# SH10_-_CAN.net
KiCad netlist of a schematic drawn in Altium Designer
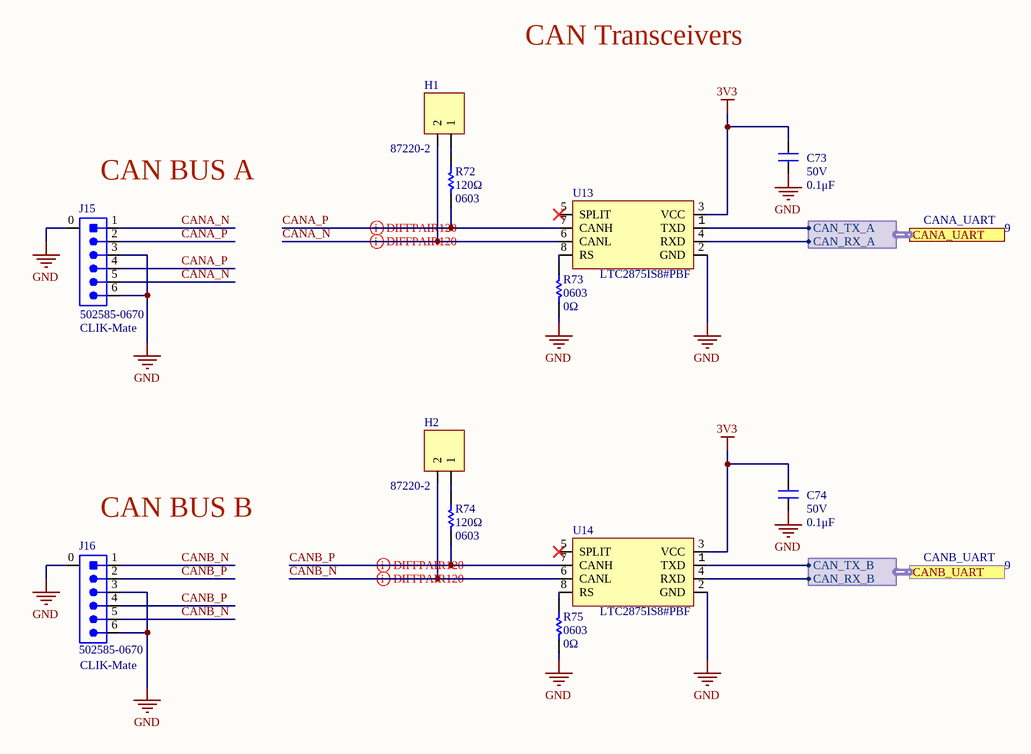
[diagram p0: SH10 - CAN.SchDoc]

(export (version "E")
  (design (tool "Eeschema 10.0.6"))
  (components
    (comp (ref "C73")
      (value "0.1μF")
      (footprint "CAP0603")
      (description "CAP CER 0.1UF 50V X7R 0603")
      (fields (field (name "VOLTAGE RATING") "50V") (field (name "Comment") "CAP_0.1uF_50V_0603"))
      (libsource (lib "UWRT_Schematic_Library_2020") (part "CAP_0.1uF_50V_0603"))
    )
    (comp (ref "C74")
      (value "0.1μF")
      (footprint "CAP0603")
      (description "CAP CER 0.1UF 50V X7R 0603")
      (fields (field (name "VOLTAGE RATING") "50V") (field (name "Comment") "CAP_0.1uF_50V_0603"))
      (libsource (lib "UWRT_Schematic_Library_2020") (part "CAP_0.1uF_50V_0603"))
    )
    (comp (ref "H1")
      (value "JUMPER_2")
      (footprint "HDR1X2")
      (description "HEADER 2X1")
      (fields (field (name "MANUFACTURER PART NUMBER 1") "87220-2"))
      (libsource (lib "UWRT_Schematic_Library_2020") (part "JUMPER_2"))
    )
    (comp (ref "H2")
      (value "JUMPER_2")
      (footprint "HDR1X2")
      (description "HEADER 2X1")
      (fields (field (name "MANUFACTURER PART NUMBER 1") "87220-2"))
      (libsource (lib "UWRT_Schematic_Library_2020") (part "JUMPER_2"))
    )
    (comp (ref "J15")
      (value "CON_6M_SM_RA_1.5mm")
      (footprint "MOLEX-5025850670")
      (description "CONN HEADER SMD RIGHT ANGLE 1.5 MM PITCH")
      (fields
        (field (name "MANUFACTOR NUMBER") "502585-0670")
        (field (name "MANUFACTURER") "Molex")
        (field (name "FAMILY") "CLIK-Mate")
      )
      (libsource (lib "UWRT_Schematic_Library_2020") (part "CON_6M_SM_RA_1.5mm"))
    )
    (comp (ref "J16")
      (value "CON_6M_SM_RA_1.5mm")
      (footprint "MOLEX-5025850670")
      (description "CONN HEADER SMD RIGHT ANGLE 1.5 MM PITCH")
      (fields
        (field (name "MANUFACTOR NUMBER") "502585-0670")
        (field (name "MANUFACTURER") "Molex")
        (field (name "FAMILY") "CLIK-Mate")
      )
      (libsource (lib "UWRT_Schematic_Library_2020") (part "CON_6M_SM_RA_1.5mm"))
    )
    (comp (ref "R72")
      (value "120Ω")
      (footprint "RESC0603(1608)_N")
      (description "RES 120 OHM 5% 1/10W 0603")
      (fields
        (field (name "TOLERANCE") "5%")
        (field (name "CASE CODE (IMPERIAL)") "0603")
        (field (name "Comment") "RES_120Ω_0603")
      )
      (libsource (lib "UWRT_Schematic_Library_2020") (part "RES_120Ω_0603_5%"))
    )
    (comp (ref "R73")
      (value "0Ω")
      (footprint "RESC0603(1608)_N")
      (description "RES 0 OHM JUMPER 1/10W 0603")
      (fields (field (name "CASE CODE (IMPERIAL)") "0603") (field (name "Comment") "RES_0Ω_0603"))
      (libsource (lib "UWRT_Schematic_Library_2020") (part "RES_0Ω_0603"))
    )
    (comp (ref "R74")
      (value "120Ω")
      (footprint "RESC0603(1608)_N")
      (description "RES 120 OHM 5% 1/10W 0603")
      (fields
        (field (name "TOLERANCE") "5%")
        (field (name "CASE CODE (IMPERIAL)") "0603")
        (field (name "Comment") "RES_120Ω_0603")
      )
      (libsource (lib "UWRT_Schematic_Library_2020") (part "RES_120Ω_0603_5%"))
    )
    (comp (ref "R75")
      (value "0Ω")
      (footprint "RESC0603(1608)_N")
      (description "RES 0 OHM JUMPER 1/10W 0603")
      (fields (field (name "CASE CODE (IMPERIAL)") "0603") (field (name "Comment") "RES_0Ω_0603"))
      (libsource (lib "UWRT_Schematic_Library_2020") (part "RES_0Ω_0603"))
    )
    (comp (ref "U13")
      (value "IC TXRX CAN")
      (footprint "LT-S8_N")
      (description "IC TXRX CAN 4MBPS 8SO")
      (fields (field (name "MANUFACTURER PART NUMBER 1") "LTC2875IS8#PBF"))
      (libsource (lib "UWRT_Schematic_Library_2020") (part "LTC2875"))
    )
    (comp (ref "U14")
      (value "IC TXRX CAN")
      (footprint "LT-S8_N")
      (description "IC TXRX CAN 4MBPS 8SO")
      (fields (field (name "MANUFACTURER PART NUMBER 1") "LTC2875IS8#PBF"))
      (libsource (lib "UWRT_Schematic_Library_2020") (part "LTC2875"))
    )
  )
  (nets
    (net (code "3") (name "/CANA_N") (class "Default")
      (node (ref "H1") (pin "2") (pinfunction "2_2") (pintype "passive"))
      (node (ref "J15") (pin "1") (pinfunction "1_1") (pintype "passive"))
      (node (ref "J15") (pin "5") (pinfunction "5_5") (pintype "passive"))
      (node (ref "U13") (pin "6") (pinfunction "CANL_6") (pintype "passive"))
    )
    (net (code "4") (name "/CANA_P") (class "Default")
      (node (ref "J15") (pin "2") (pinfunction "2_2") (pintype "passive"))
      (node (ref "J15") (pin "4") (pinfunction "4_4") (pintype "passive"))
      (node (ref "R72") (pin "1") (pinfunction "1_1") (pintype "passive"))
      (node (ref "U13") (pin "7") (pinfunction "CANH_7") (pintype "passive"))
    )
    (net (code "5") (name "/CANB_N") (class "Default")
      (node (ref "H2") (pin "2") (pinfunction "2_2") (pintype "passive"))
      (node (ref "J16") (pin "1") (pinfunction "1_1") (pintype "passive"))
      (node (ref "J16") (pin "5") (pinfunction "5_5") (pintype "passive"))
      (node (ref "U14") (pin "6") (pinfunction "CANL_6") (pintype "passive"))
    )
    (net (code "6") (name "/CANB_P") (class "Default")
      (node (ref "J16") (pin "2") (pinfunction "2_2") (pintype "passive"))
      (node (ref "J16") (pin "4") (pinfunction "4_4") (pintype "passive"))
      (node (ref "R74") (pin "1") (pinfunction "1_1") (pintype "passive"))
      (node (ref "U14") (pin "7") (pinfunction "CANH_7") (pintype "passive"))
    )
    (net (code "7") (name "/CAN_RX_A") (class "Default")
      (node (ref "U13") (pin "4") (pinfunction "RXD_4") (pintype "passive"))
    )
    (net (code "8") (name "/CAN_RX_B") (class "Default")
      (node (ref "U14") (pin "4") (pinfunction "RXD_4") (pintype "passive"))
    )
    (net (code "9") (name "/CAN_TX_A") (class "Default")
      (node (ref "U13") (pin "1") (pinfunction "TXD_1") (pintype "passive"))
    )
    (net (code "10") (name "/CAN_TX_B") (class "Default")
      (node (ref "U14") (pin "1") (pinfunction "TXD_1") (pintype "passive"))
    )
    (net (code "13") (name "3V3") (class "Default")
      (node (ref "C73") (pin "1") (pinfunction "1_1") (pintype "passive"))
      (node (ref "C74") (pin "1") (pinfunction "1_1") (pintype "passive"))
      (node (ref "U13") (pin "3") (pinfunction "VCC_3") (pintype "passive"))
      (node (ref "U14") (pin "3") (pinfunction "VCC_3") (pintype "passive"))
    )
    (net (code "14") (name "GND") (class "Default")
      (node (ref "C73") (pin "2") (pinfunction "2_2") (pintype "passive"))
      (node (ref "C74") (pin "2") (pinfunction "2_2") (pintype "passive"))
      (node (ref "J15") (pin "0") (pinfunction "0_0") (pintype "passive"))
      (node (ref "J15") (pin "3") (pinfunction "3_3") (pintype "passive"))
      (node (ref "J15") (pin "6") (pinfunction "6_6") (pintype "passive"))
      (node (ref "J16") (pin "0") (pinfunction "0_0") (pintype "passive"))
      (node (ref "J16") (pin "3") (pinfunction "3_3") (pintype "passive"))
      (node (ref "J16") (pin "6") (pinfunction "6_6") (pintype "passive"))
      (node (ref "R73") (pin "1") (pinfunction "1_1") (pintype "passive"))
      (node (ref "R75") (pin "1") (pinfunction "1_1") (pintype "passive"))
      (node (ref "U13") (pin "2") (pinfunction "GND_2") (pintype "passive"))
      (node (ref "U14") (pin "2") (pinfunction "GND_2") (pintype "passive"))
    )
    (net (code "15") (name "Net-(H1-Pad1)") (class "Default")
      (node (ref "H1") (pin "1") (pinfunction "1_1") (pintype "passive"))
      (node (ref "R72") (pin "2") (pinfunction "2_2") (pintype "passive"))
    )
    (net (code "16") (name "Net-(H2-Pad1)") (class "Default")
      (node (ref "H2") (pin "1") (pinfunction "1_1") (pintype "passive"))
      (node (ref "R74") (pin "2") (pinfunction "2_2") (pintype "passive"))
    )
    (net (code "17") (name "Net-(U13-RS)") (class "Default")
      (node (ref "R73") (pin "2") (pinfunction "2_2") (pintype "passive"))
      (node (ref "U13") (pin "8") (pinfunction "RS_8") (pintype "passive"))
    )
    (net (code "18") (name "Net-(U14-RS)") (class "Default")
      (node (ref "R75") (pin "2") (pinfunction "2_2") (pintype "passive"))
      (node (ref "U14") (pin "8") (pinfunction "RS_8") (pintype "passive"))
    )
    (net (code "19") (name "unconnected-(U13-SPLIT-Pad5)") (class "Default")
      (node (ref "U13") (pin "5") (pinfunction "SPLIT_5") (pintype "passive+no_connect"))
    )
    (net (code "20") (name "unconnected-(U14-SPLIT-Pad5)") (class "Default")
      (node (ref "U14") (pin "5") (pinfunction "SPLIT_5") (pintype "passive+no_connect"))
    )
  )
)
